# test4.net
KiCad netlist of a schematic drawn in EAGLE
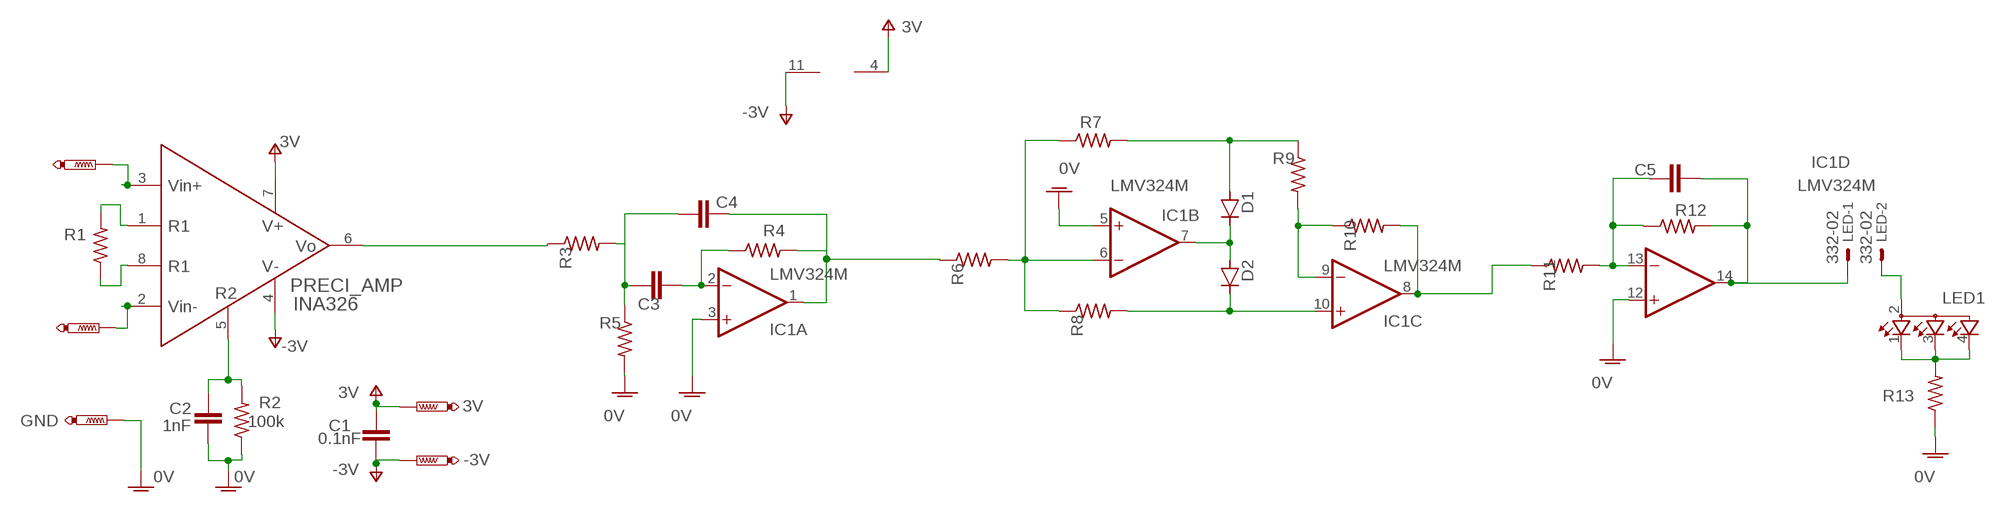
[diagram p0: schematic, sheet 1]

(export (version "E")
  (design (tool "Eeschema 10.0.6"))
  (components
    (comp (ref "-3V")
      (value "PTR1PAD1-13")
      (footprint "eagle-import:P1-13")
      (libsource (lib "eagle-import") (part "PTR1PAD1-13"))
    )
    (comp (ref "3V")
      (value "PTR1PAD1-13")
      (footprint "eagle-import:P1-13")
      (libsource (lib "eagle-import") (part "PTR1PAD1-13"))
    )
    (comp (ref "C1")
      (value "0.1nF")
      (footprint "eagle-import:C0603")
      (libsource (lib "eagle-import") (part "C-EUC0603"))
    )
    (comp (ref "C2")
      (value "1nF")
      (footprint "eagle-import:C0603")
      (libsource (lib "eagle-import") (part "C-EUC0603"))
    )
    (comp (ref "C3")
      (value "0.1nF")
      (footprint "eagle-import:C0603")
      (libsource (lib "eagle-import") (part "C-EUC0603"))
    )
    (comp (ref "C4")
      (value "0.1nF")
      (footprint "eagle-import:C0603")
      (libsource (lib "eagle-import") (part "C-EUC0603"))
    )
    (comp (ref "C5")
      (value "0.1nF")
      (footprint "eagle-import:C0603")
      (libsource (lib "eagle-import") (part "C-EUC0603"))
    )
    (comp (ref "D1")
      (value "D-SOD-80")
      (footprint "eagle-import:SOD80")
      (libsource (lib "eagle-import") (part "D-SOD-80"))
    )
    (comp (ref "D2")
      (value "D-SOD-80")
      (footprint "eagle-import:SOD80")
      (libsource (lib "eagle-import") (part "D-SOD-80"))
    )
    (comp (ref "GND")
      (value "PTR1PAD1-13")
      (footprint "eagle-import:P1-13")
      (libsource (lib "eagle-import") (part "PTR1PAD1-13"))
    )
    (comp (ref "IC1")
      (value "LMV324M")
      (footprint "eagle-import:SO14")
      (fields (field (name "SPICEPREFIX") "J"))
      (libsource (lib "eagle-import") (part "LMV324?M"))
    )
    (comp (ref "IN+")
      (value "PTR1PAD1-13")
      (footprint "eagle-import:P1-13")
      (libsource (lib "eagle-import") (part "PTR1PAD1-13"))
    )
    (comp (ref "IN-")
      (value "PTR1PAD1-13")
      (footprint "eagle-import:P1-13")
      (libsource (lib "eagle-import") (part "PTR1PAD1-13"))
    )
    (comp (ref "LED")
      (value "332-02")
      (footprint "eagle-import:332-02")
      (libsource (lib "eagle-import") (part "332-02"))
    )
    (comp (ref "LED1")
      (value "TOPLED-3")
      (footprint "eagle-import:P-LCC-4-3")
      (libsource (lib "eagle-import") (part "TOPLED-3"))
    )
    (comp (ref "PRECI_AMP")
      (value "INA326")
      (footprint "eagle-import:SOP65P490X110-8N")
      (fields
        (field (name "DIGI-KEY_PART_NUMBER") "296-15312-1-ND")
        (field (name "MF") "Texas Instruments")
        (field (name "MP") "INA326EA/250")
        (field (name "MP_1") "INA326")
      )
      (libsource (lib "eagle-import") (part "INA326EA/250"))
    )
    (comp (ref "R1")
      (value "100k")
      (footprint "eagle-import:R0603")
      (libsource (lib "eagle-import") (part "R-US_R0603"))
    )
    (comp (ref "R2")
      (value "100k")
      (footprint "eagle-import:R0603")
      (libsource (lib "eagle-import") (part "R-US_R0603"))
    )
    (comp (ref "R3")
      (value "100k")
      (footprint "eagle-import:R0603")
      (libsource (lib "eagle-import") (part "R-US_R0603"))
    )
    (comp (ref "R4")
      (value "100k")
      (footprint "eagle-import:R0603")
      (libsource (lib "eagle-import") (part "R-US_R0603"))
    )
    (comp (ref "R5")
      (value "100k")
      (footprint "eagle-import:R0603")
      (libsource (lib "eagle-import") (part "R-US_R0603"))
    )
    (comp (ref "R6")
      (value "100k")
      (footprint "eagle-import:R0603")
      (libsource (lib "eagle-import") (part "R-US_R0603"))
    )
    (comp (ref "R7")
      (value "100k")
      (footprint "eagle-import:R0603")
      (libsource (lib "eagle-import") (part "R-US_R0603"))
    )
    (comp (ref "R8")
      (value "100k")
      (footprint "eagle-import:R0603")
      (libsource (lib "eagle-import") (part "R-US_R0603"))
    )
    (comp (ref "R9")
      (value "100k")
      (footprint "eagle-import:R0603")
      (libsource (lib "eagle-import") (part "R-US_R0603"))
    )
    (comp (ref "R10")
      (value "100k")
      (footprint "eagle-import:R0603")
      (libsource (lib "eagle-import") (part "R-US_R0603"))
    )
    (comp (ref "R11")
      (value "100k")
      (footprint "eagle-import:R0603")
      (libsource (lib "eagle-import") (part "R-US_R0603"))
    )
    (comp (ref "R12")
      (value "100k")
      (footprint "eagle-import:R0603")
      (libsource (lib "eagle-import") (part "R-US_R0603"))
    )
    (comp (ref "R13")
      (value "100k")
      (footprint "eagle-import:R0603")
      (libsource (lib "eagle-import") (part "R-US_R0603"))
    )
  )
  (nets
    (net (code "1") (name "-3V") (class "Default")
      (node (ref "-3V") (pin "TP") (pinfunction "TP_TP") (pintype "input"))
      (node (ref "C1") (pin "2") (pinfunction "2_2") (pintype "passive"))
      (node (ref "IC1") (pin "11") (pinfunction "V-_11") (pintype "power_in"))
      (node (ref "PRECI_AMP") (pin "4") (pinfunction "V-_4") (pintype "power_in"))
    )
    (net (code "2") (name "0V") (class "Default")
      (node (ref "C2") (pin "1") (pinfunction "1_1") (pintype "passive"))
      (node (ref "GND") (pin "TP") (pinfunction "TP_TP") (pintype "input"))
      (node (ref "IC1") (pin "12") (pinfunction "+IN_12") (pintype "input"))
      (node (ref "IC1") (pin "3") (pinfunction "+IN_3") (pintype "input"))
      (node (ref "IC1") (pin "5") (pinfunction "+IN_5") (pintype "input"))
      (node (ref "R13") (pin "1") (pinfunction "1_1") (pintype "passive"))
      (node (ref "R2") (pin "1") (pinfunction "1_1") (pintype "passive"))
      (node (ref "R5") (pin "2") (pinfunction "2_2") (pintype "passive"))
    )
    (net (code "3") (name "3V") (class "Default")
      (node (ref "3V") (pin "TP") (pinfunction "TP_TP") (pintype "input"))
      (node (ref "C1") (pin "1") (pinfunction "1_1") (pintype "passive"))
      (node (ref "IC1") (pin "4") (pinfunction "V+_4") (pintype "power_in"))
      (node (ref "PRECI_AMP") (pin "7") (pinfunction "V+_7") (pintype "power_in"))
    )
    (net (code "4") (name "Net-(C3-Pad2)") (class "Default")
      (node (ref "C3") (pin "2") (pinfunction "2_2") (pintype "passive"))
      (node (ref "C4") (pin "2") (pinfunction "2_2") (pintype "passive"))
      (node (ref "R3") (pin "2") (pinfunction "2_2") (pintype "passive"))
      (node (ref "R5") (pin "1") (pinfunction "1_1") (pintype "passive"))
    )
    (net (code "5") (name "Net-(D1-A)") (class "Default")
      (node (ref "D1") (pin "2") (pinfunction "A_2") (pintype "passive"))
      (node (ref "R7") (pin "2") (pinfunction "2_2") (pintype "passive"))
      (node (ref "R9") (pin "1") (pinfunction "1_1") (pintype "passive"))
    )
    (net (code "6") (name "Net-(D1-C)") (class "Default")
      (node (ref "D1") (pin "1") (pinfunction "C_1") (pintype "passive"))
      (node (ref "D2") (pin "2") (pinfunction "A_2") (pintype "passive"))
      (node (ref "IC1") (pin "7") (pinfunction "OUT_7") (pintype "output"))
    )
    (net (code "7") (name "Net-(D2-C)") (class "Default")
      (node (ref "D2") (pin "1") (pinfunction "C_1") (pintype "passive"))
      (node (ref "IC1") (pin "10") (pinfunction "+IN_10") (pintype "input"))
      (node (ref "R8") (pin "2") (pinfunction "2_2") (pintype "passive"))
    )
    (net (code "8") (name "Net-(IC1A--IN)") (class "Default")
      (node (ref "C3") (pin "1") (pinfunction "1_1") (pintype "passive"))
      (node (ref "IC1") (pin "2") (pinfunction "-IN_2") (pintype "input"))
      (node (ref "R4") (pin "1") (pinfunction "1_1") (pintype "passive"))
    )
    (net (code "9") (name "Net-(IC1A-OUT)") (class "Default")
      (node (ref "C4") (pin "1") (pinfunction "1_1") (pintype "passive"))
      (node (ref "IC1") (pin "1") (pinfunction "OUT_1") (pintype "output"))
      (node (ref "R4") (pin "2") (pinfunction "2_2") (pintype "passive"))
      (node (ref "R6") (pin "1") (pinfunction "1_1") (pintype "passive"))
    )
    (net (code "10") (name "Net-(IC1B--IN)") (class "Default")
      (node (ref "IC1") (pin "6") (pinfunction "-IN_6") (pintype "input"))
      (node (ref "R6") (pin "2") (pinfunction "2_2") (pintype "passive"))
      (node (ref "R7") (pin "1") (pinfunction "1_1") (pintype "passive"))
      (node (ref "R8") (pin "1") (pinfunction "1_1") (pintype "passive"))
    )
    (net (code "11") (name "Net-(IC1C--IN)") (class "Default")
      (node (ref "IC1") (pin "9") (pinfunction "-IN_9") (pintype "input"))
      (node (ref "R10") (pin "1") (pinfunction "1_1") (pintype "passive"))
      (node (ref "R9") (pin "2") (pinfunction "2_2") (pintype "passive"))
    )
    (net (code "12") (name "Net-(IC1C-OUT)") (class "Default")
      (node (ref "IC1") (pin "8") (pinfunction "OUT_8") (pintype "output"))
      (node (ref "R10") (pin "2") (pinfunction "2_2") (pintype "passive"))
      (node (ref "R11") (pin "1") (pinfunction "1_1") (pintype "passive"))
    )
    (net (code "13") (name "Net-(IC1D--IN)") (class "Default")
      (node (ref "C5") (pin "1") (pinfunction "1_1") (pintype "passive"))
      (node (ref "IC1") (pin "13") (pinfunction "-IN_13") (pintype "input"))
      (node (ref "R11") (pin "2") (pinfunction "2_2") (pintype "passive"))
      (node (ref "R12") (pin "1") (pinfunction "1_1") (pintype "passive"))
    )
    (net (code "14") (name "Net-(IC1D-OUT)") (class "Default")
      (node (ref "C5") (pin "2") (pinfunction "2_2") (pintype "passive"))
      (node (ref "IC1") (pin "14") (pinfunction "OUT_14") (pintype "output"))
      (node (ref "LED") (pin "1") (pinfunction "S_1") (pintype "passive"))
      (node (ref "R12") (pin "2") (pinfunction "2_2") (pintype "passive"))
    )
    (net (code "15") (name "Net-(LED1-A2)") (class "Default")
      (node (ref "LED") (pin "2") (pinfunction "S_2") (pintype "passive"))
      (node (ref "LED1") (pin "2") (pinfunction "A2_2") (pintype "passive"))
    )
    (net (code "16") (name "Net-(LED1-CBLUE)") (class "Default")
      (node (ref "LED1") (pin "1") (pinfunction "CRED_1") (pintype "passive"))
      (node (ref "LED1") (pin "3") (pinfunction "CBLUE_3") (pintype "passive"))
      (node (ref "LED1") (pin "4") (pinfunction "CGREEN_4") (pintype "passive"))
      (node (ref "R13") (pin "2") (pinfunction "2_2") (pintype "passive"))
    )
    (net (code "17") (name "Net-(PRECI_AMP-R1)") (class "Default")
      (node (ref "PRECI_AMP") (pin "8") (pinfunction "R1_8") (pintype "input"))
      (node (ref "R1") (pin "1") (pinfunction "1_1") (pintype "passive"))
    )
    (net (code "18") (name "Net-(PRECI_AMP-R1_2)") (class "Default")
      (node (ref "PRECI_AMP") (pin "1") (pinfunction "R1_2_1") (pintype "input"))
      (node (ref "R1") (pin "2") (pinfunction "2_2") (pintype "passive"))
    )
    (net (code "19") (name "Net-(PRECI_AMP-R2)") (class "Default")
      (node (ref "C2") (pin "2") (pinfunction "2_2") (pintype "passive"))
      (node (ref "PRECI_AMP") (pin "5") (pinfunction "R2_5") (pintype "input"))
      (node (ref "R2") (pin "2") (pinfunction "2_2") (pintype "passive"))
    )
    (net (code "20") (name "Net-(PRECI_AMP-VIN+)") (class "Default")
      (node (ref "IN+") (pin "TP") (pinfunction "TP_TP") (pintype "input"))
      (node (ref "PRECI_AMP") (pin "3") (pinfunction "VIN+_3") (pintype "input"))
    )
    (net (code "21") (name "Net-(PRECI_AMP-VIN-)") (class "Default")
      (node (ref "IN-") (pin "TP") (pinfunction "TP_TP") (pintype "input"))
      (node (ref "PRECI_AMP") (pin "2") (pinfunction "VIN-_2") (pintype "input"))
    )
    (net (code "22") (name "Net-(PRECI_AMP-VO)") (class "Default")
      (node (ref "PRECI_AMP") (pin "6") (pinfunction "VO_6") (pintype "output"))
      (node (ref "R3") (pin "1") (pinfunction "1_1") (pintype "passive"))
    )
  )
)
